# DS2480B-DONGLE.net
KiCad netlist of a schematic drawn in Altium Designer
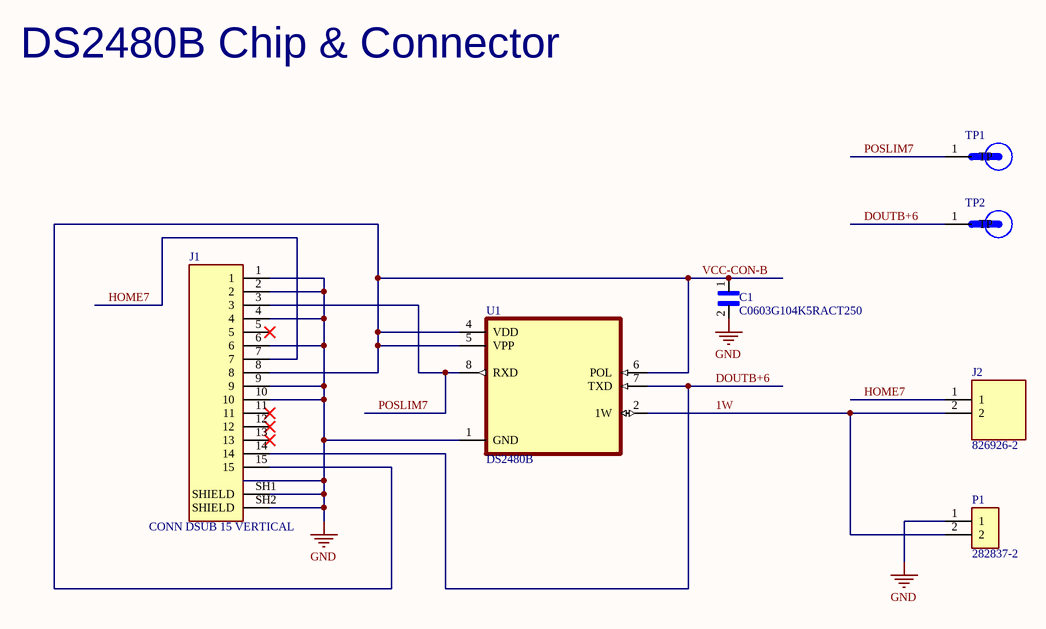
[diagram p0: DS2480B-DONGLE.SchDoc]

(export (version "E")
  (design (tool "Eeschema 10.0.6"))
  (components
    (comp (ref "C1")
      (value "C0603G104K5RACT250")
      (footprint "C0603G104K5RACT250:CAPC1608X90")
      (description "Multilayer Ceramic Capacitors MLCC - SMD/SMT 50V 0.1uF 0603 X7R 0.1")
      (fields (field (name "MF") "Kemet"))
      (libsource (lib "C0603G104K5RACT250") (part "C0603G104K5RACT250"))
    )
    (comp (ref "J1")
      (value "CONN DSUB 15 VERTICAL")
      (footprint "DSUBHDVPTMOS15:CONN_1734530-3")
      (description "15 Position D-Sub, High Density Receptacle, Female Sockets Connector")
      (fields (field (name "MP") "1734530-3") (field (name "MF") "TE Connectivity"))
      (libsource (lib "DSUBHDVPTMOS15") (part "1734530-3"))
    )
    (comp (ref "J2")
      (value "826926-2")
      (footprint "Header-2P:TE_826926-2")
      (description "Pin header; pin strips; AMPMODU MOD II; male; PIN: 2; straight")
      (fields (field (name "MF") "TE Connectivity"))
      (libsource (lib "Header-2P") (part "826926-2"))
    )
    (comp (ref "P1")
      (value "282837-2")
      (footprint "TE_282837-2:TE_282837-2")
      (description "Connector Terminal Blocks Receptacle 2 Position 5.08mm Solder Straight Thru-Hole 13.5A/Contact")
      (fields (field (name "MF") "TE Connectivity"))
      (libsource (lib "282837-2") (part "282837-2"))
    )
    (comp (ref "TP1")
      (value "~")
      (footprint "test_point:TP380X203")
      (description "PC Test Point, Miniature Phosphor Bronze, Silver Plating Surface Mount Mounting Type")
      (fields (field (name "MP") "5019") (field (name "MF") "Keystone Electronics"))
      (libsource (lib "test_point") (part "5019"))
    )
    (comp (ref "TP2")
      (value "~")
      (footprint "test_point:TP380X203")
      (description "PC Test Point, Miniature Phosphor Bronze, Silver Plating Surface Mount Mounting Type")
      (fields (field (name "MP") "5019") (field (name "MF") "Keystone Electronics"))
      (libsource (lib "test_point") (part "5019"))
    )
    (comp (ref "U1")
      (value "DS2480B")
      (footprint "DS2480B:SOIC127P600X175-8N")
      (description "1/0 Driver RS232 8-SOIC")
      (fields (field (name "MF") "Maxim Integrated"))
      (libsource (lib "DS2480B") (part "DS2480B"))
    )
  )
  (nets
    (net (code "1") (name "/1W") (class "Default")
      (node (ref "J2") (pin "2") (pinfunction "2_2") (pintype "passive"))
      (node (ref "P1") (pin "2") (pinfunction "2_2") (pintype "passive"))
      (node (ref "U1") (pin "2") (pinfunction "1W_2") (pintype "bidirectional"))
    )
    (net (code "2") (name "/DOUTB+6") (class "Default")
      (node (ref "J1") (pin "14") (pinfunction "14_14") (pintype "passive"))
      (node (ref "TP2") (pin "1") (pinfunction "TP_1") (pintype "passive"))
      (node (ref "U1") (pin "7") (pinfunction "TXD_7") (pintype "input"))
    )
    (net (code "3") (name "/HOME7") (class "Default")
      (node (ref "J1") (pin "7") (pinfunction "7_7") (pintype "passive"))
      (node (ref "J2") (pin "1") (pinfunction "1_1") (pintype "passive"))
    )
    (net (code "4") (name "/POSLIM7") (class "Default")
      (node (ref "J1") (pin "3") (pinfunction "3_3") (pintype "passive"))
      (node (ref "TP1") (pin "1") (pinfunction "TP_1") (pintype "passive"))
      (node (ref "U1") (pin "8") (pinfunction "RXD_8") (pintype "output"))
    )
    (net (code "5") (name "/VCC-CON-B") (class "Default")
      (node (ref "C1") (pin "1") (pinfunction "1_1") (pintype "passive"))
      (node (ref "J1") (pin "15") (pinfunction "15_15") (pintype "passive"))
      (node (ref "J1") (pin "8") (pinfunction "8_8") (pintype "passive"))
      (node (ref "U1") (pin "4") (pinfunction "VDD_4") (pintype "power_in"))
      (node (ref "U1") (pin "5") (pinfunction "VPP_5") (pintype "power_in"))
      (node (ref "U1") (pin "6") (pinfunction "POL_6") (pintype "input"))
    )
    (net (code "6") (name "GND") (class "Default")
      (node (ref "C1") (pin "2") (pinfunction "2_2") (pintype "passive"))
      (node (ref "J1") (pin "1") (pinfunction "1_1") (pintype "passive"))
      (node (ref "J1") (pin "10") (pinfunction "10_10") (pintype "passive"))
      (node (ref "J1") (pin "2") (pinfunction "2_2") (pintype "passive"))
      (node (ref "J1") (pin "4") (pinfunction "4_4") (pintype "passive"))
      (node (ref "J1") (pin "6") (pinfunction "6_6") (pintype "passive"))
      (node (ref "J1") (pin "9") (pinfunction "9_9") (pintype "passive"))
      (node (ref "J1") (pin "SH1") (pinfunction "SHIELD_SH1") (pintype "passive"))
      (node (ref "J1") (pin "SH2") (pinfunction "SHIELD_SH2") (pintype "passive"))
      (node (ref "P1") (pin "1") (pinfunction "1_1") (pintype "passive"))
      (node (ref "U1") (pin "1") (pinfunction "GND_1") (pintype "power_in"))
    )
    (net (code "7") (name "unconnected-(J1-Pad5)") (class "Default")
      (node (ref "J1") (pin "5") (pinfunction "5_5") (pintype "passive+no_connect"))
    )
    (net (code "8") (name "unconnected-(J1-Pad11)") (class "Default")
      (node (ref "J1") (pin "11") (pinfunction "11_11") (pintype "passive+no_connect"))
    )
    (net (code "9") (name "unconnected-(J1-Pad12)") (class "Default")
      (node (ref "J1") (pin "12") (pinfunction "12_12") (pintype "passive+no_connect"))
    )
    (net (code "10") (name "unconnected-(J1-Pad13)") (class "Default")
      (node (ref "J1") (pin "13") (pinfunction "13_13") (pintype "passive+no_connect"))
    )
  )
)
